# current_monitor_v1-2.net
KiCad netlist of a schematic drawn in EAGLE
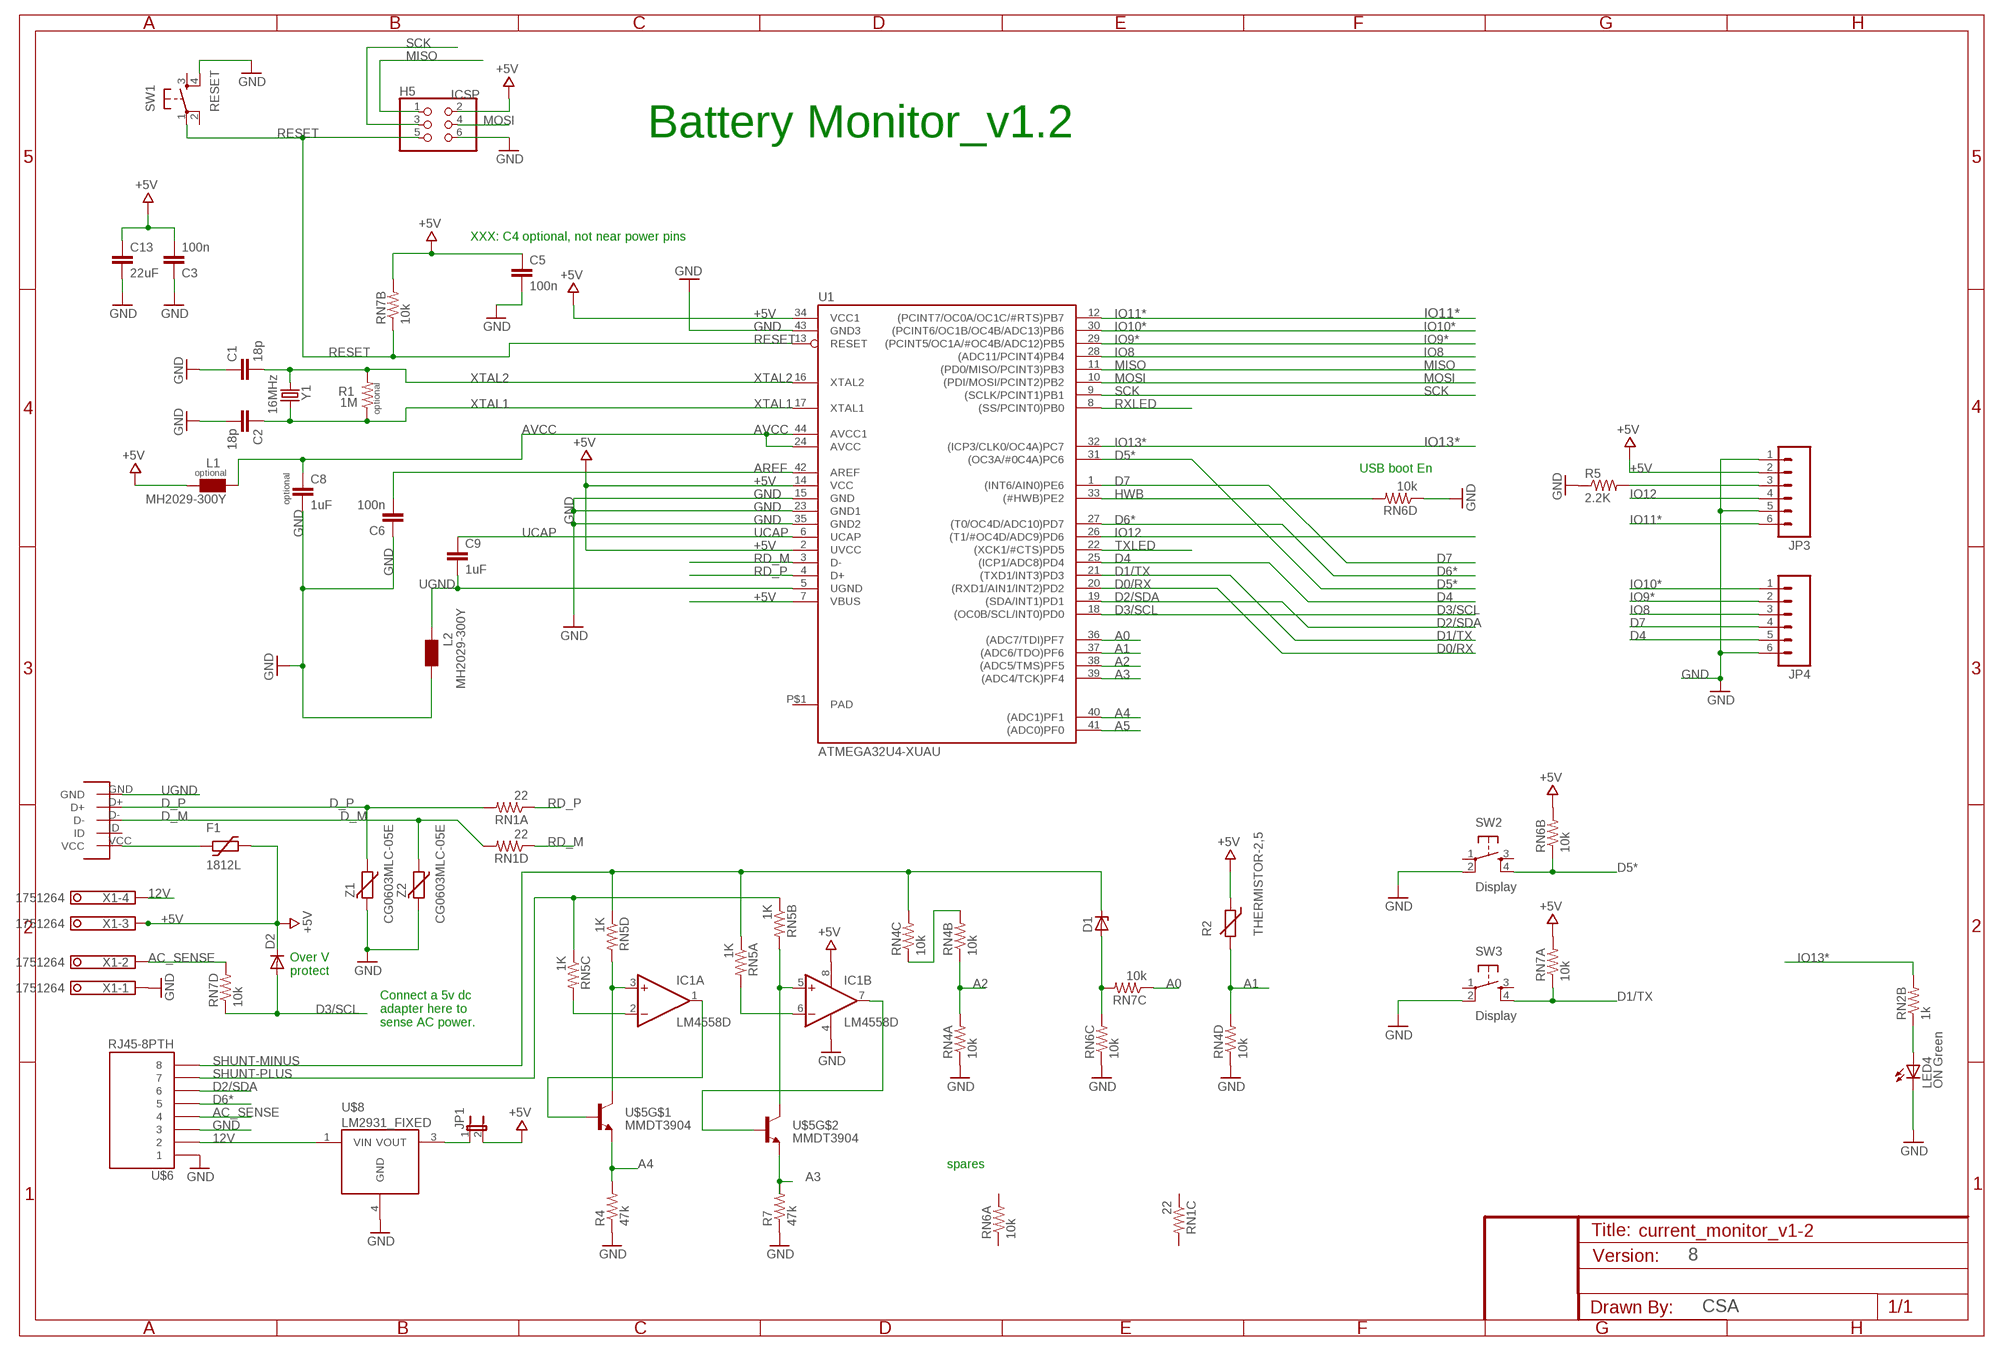
[diagram p0: schematic, sheet 1]

(export (version "E")
  (design (tool "Eeschema 10.0.6"))
  (components
    (comp (ref "C1")
      (value "18p")
      (footprint "eagle-import:0805")
      (libsource (lib "eagle-import") (part "CAP0805"))
    )
    (comp (ref "C2")
      (value "18p")
      (footprint "eagle-import:0805")
      (libsource (lib "eagle-import") (part "CAP0805"))
    )
    (comp (ref "C3")
      (value "100n")
      (footprint "eagle-import:0805")
      (libsource (lib "eagle-import") (part "CAP0805"))
    )
    (comp (ref "C5")
      (value "100n")
      (footprint "eagle-import:0805")
      (libsource (lib "eagle-import") (part "CAP0805"))
    )
    (comp (ref "C6")
      (value "100n")
      (footprint "eagle-import:0805")
      (libsource (lib "eagle-import") (part "CAP0805"))
    )
    (comp (ref "C8")
      (value "1uF")
      (footprint "eagle-import:0805")
      (libsource (lib "eagle-import") (part "CAP0805"))
    )
    (comp (ref "C9")
      (value "1uF")
      (footprint "eagle-import:0805")
      (libsource (lib "eagle-import") (part "CAP0805"))
    )
    (comp (ref "C13")
      (value "22uF")
      (footprint "eagle-import:1206")
      (libsource (lib "eagle-import") (part "CAP1206"))
    )
    (comp (ref "D1")
      (value "ZENER-DIODEZD-5")
      (footprint "eagle-import:ZDIO-5")
      (libsource (lib "eagle-import") (part "ZENER-DIODEZD-5"))
    )
    (comp (ref "D2")
      (value "DIODESMA")
      (footprint "eagle-import:SMA-DIODE")
      (libsource (lib "eagle-import") (part "DIODESMA"))
    )
    (comp (ref "F1")
      (value "1812L")
      (footprint "eagle-import:1812L")
      (libsource (lib "eagle-import") (part "1812L"))
    )
    (comp (ref "H5")
      (value "ICSP")
      (footprint "eagle-import:2X03")
      (libsource (lib "eagle-import") (part "PINHD-2X3"))
    )
    (comp (ref "IC1")
      (value "LM4558D")
      (footprint "eagle-import:SO08")
      (libsource (lib "eagle-import") (part "4558DLM"))
    )
    (comp (ref "JP1")
      (value "JUMPER-2-OLDPTH_LOCK")
      (footprint "eagle-import:1X02_LOCK")
      (libsource (lib "eagle-import") (part "JUMPER-2-OLDPTH_LOCK"))
    )
    (comp (ref "JP3")
      (value "M06FEMALE_LOCK")
      (footprint "eagle-import:1X06_FEMALE_LOCK.010")
      (libsource (lib "eagle-import") (part "M06FEMALE_LOCK"))
    )
    (comp (ref "JP4")
      (value "M06FEMALE_LOCK")
      (footprint "eagle-import:1X06_FEMALE_LOCK.010")
      (libsource (lib "eagle-import") (part "M06FEMALE_LOCK"))
    )
    (comp (ref "L1")
      (value "MH2029-300Y")
      (footprint "eagle-import:0805")
      (libsource (lib "eagle-import") (part "WE-CBF_0805"))
    )
    (comp (ref "L2")
      (value "MH2029-300Y")
      (footprint "eagle-import:0805")
      (libsource (lib "eagle-import") (part "WE-CBF_0805"))
    )
    (comp (ref "LED4")
      (value "ON Green")
      (footprint "eagle-import:LED0805")
      (libsource (lib "eagle-import") (part "LED0805"))
    )
    (comp (ref "R1")
      (value "1M")
      (footprint "eagle-import:0805")
      (libsource (lib "eagle-import") (part "RESISTOR0805-RES"))
    )
    (comp (ref "R2")
      (value "THERMISTOR-2,5")
      (footprint "eagle-import:RS-2,5")
      (libsource (lib "eagle-import") (part "THERMISTOR-2,5"))
    )
    (comp (ref "R4")
      (value "47k")
      (footprint "eagle-import:0805")
      (libsource (lib "eagle-import") (part "RESISTOR0805-RES"))
    )
    (comp (ref "R5")
      (value "2.2K")
      (footprint "eagle-import:0805")
      (libsource (lib "eagle-import") (part "RESISTOR0805-RES"))
    )
    (comp (ref "R7")
      (value "47k")
      (footprint "eagle-import:0805")
      (libsource (lib "eagle-import") (part "RESISTOR0805-RES"))
    )
    (comp (ref "RN1")
      (value "22")
      (footprint "eagle-import:CRA06S")
      (libsource (lib "eagle-import") (part "RESISTOR-ARRAYCRA06S"))
    )
    (comp (ref "RN2")
      (value "1k")
      (footprint "eagle-import:CRA06S")
      (libsource (lib "eagle-import") (part "RESISTOR-ARRAYCRA06S"))
    )
    (comp (ref "RN4")
      (value "10k")
      (footprint "eagle-import:CRA06S")
      (libsource (lib "eagle-import") (part "RESISTOR-ARRAYCRA06S"))
    )
    (comp (ref "RN5")
      (value "1K")
      (footprint "eagle-import:CRA06S")
      (libsource (lib "eagle-import") (part "RESISTOR-ARRAYCRA06S"))
    )
    (comp (ref "RN6")
      (value "10k")
      (footprint "eagle-import:CRA06S")
      (libsource (lib "eagle-import") (part "RESISTOR-ARRAYCRA06S"))
    )
    (comp (ref "RN7")
      (value "10k")
      (footprint "eagle-import:CRA06S")
      (libsource (lib "eagle-import") (part "RESISTOR-ARRAYCRA06S"))
    )
    (comp (ref "SW1")
      (value "RESET")
      (footprint "eagle-import:TACTILE-PTH")
      (libsource (lib "eagle-import") (part "TAC_SWITCHPTH"))
    )
    (comp (ref "SW2")
      (value "Display")
      (footprint "eagle-import:TACTILE-PTH")
      (libsource (lib "eagle-import") (part "TAC_SWITCHPTH"))
    )
    (comp (ref "SW3")
      (value "Display")
      (footprint "eagle-import:TACTILE-PTH")
      (libsource (lib "eagle-import") (part "TAC_SWITCHPTH"))
    )
    (comp (ref "U$5")
      (value "MMDT3904")
      (footprint "eagle-import:SOT363")
      (libsource (lib "eagle-import") (part "MMDT3904"))
    )
    (comp (ref "U$6")
      (value "RJ45-8PTH")
      (footprint "eagle-import:RJ45-8")
      (libsource (lib "eagle-import") (part "RJ45-8PTH"))
    )
    (comp (ref "U$8")
      (value "LM2931_FIXED")
      (footprint "eagle-import:DPAK")
      (libsource (lib "eagle-import") (part "LM2931_FIXED"))
    )
    (comp (ref "U$16")
      (value "USB-MICRO-B-DIGIKEY")
      (footprint "eagle-import:USB-MICRO-B-DIGIKEY")
      (libsource (lib "eagle-import") (part "USB-MICRO-B-DIGIKEY"))
    )
    (comp (ref "U1")
      (value "ATMEGA32U4-XUAU")
      (footprint "eagle-import:TQFP44-PAD")
      (libsource (lib "eagle-import") (part "ATMEGA32U4-XUAU"))
    )
    (comp (ref "X1")
      (value "1751264")
      (footprint "eagle-import:1751264")
      (libsource (lib "eagle-import") (part "1751264"))
    )
    (comp (ref "Y1")
      (value "16MHz")
      (footprint "eagle-import:HC49US")
      (libsource (lib "eagle-import") (part "CRYSTALHC49US"))
    )
    (comp (ref "Z1")
      (value "CG0603MLC-05E")
      (footprint "eagle-import:CT_CN0603")
      (libsource (lib "eagle-import") (part "VARISTORCN0603"))
    )
    (comp (ref "Z2")
      (value "CG0603MLC-05E")
      (footprint "eagle-import:CT_CN0603")
      (libsource (lib "eagle-import") (part "VARISTORCN0603"))
    )
  )
  (nets
    (net (code "1") (name "+5V") (class "Default")
      (node (ref "C13") (pin "1") (pinfunction "1_1") (pintype "passive"))
      (node (ref "C3") (pin "2") (pinfunction "2_2") (pintype "passive"))
      (node (ref "C5") (pin "1") (pinfunction "1_1") (pintype "passive"))
      (node (ref "D2") (pin "C") (pinfunction "C_C") (pintype "passive"))
      (node (ref "F1") (pin "P$2") (pinfunction "2_P$2") (pintype "passive"))
      (node (ref "H5") (pin "2") (pinfunction "2_2") (pintype "passive"))
      (node (ref "IC1") (pin "8") (pinfunction "V+_8") (pintype "power_in"))
      (node (ref "JP1") (pin "2") (pinfunction "2_2") (pintype "passive"))
      (node (ref "JP3") (pin "2") (pinfunction "2_2") (pintype "passive"))
      (node (ref "L1") (pin "1") (pinfunction "1_1") (pintype "passive"))
      (node (ref "R2") (pin "1") (pinfunction "1_1") (pintype "passive"))
      (node (ref "RN6") (pin "7") (pinfunction "2_7") (pintype "passive"))
      (node (ref "RN7") (pin "7") (pinfunction "2_7") (pintype "passive"))
      (node (ref "RN7") (pin "8") (pinfunction "2_8") (pintype "passive"))
      (node (ref "U1") (pin "14") (pinfunction "VCC_14") (pintype "power_in"))
      (node (ref "U1") (pin "2") (pinfunction "UVCC_2") (pintype "power_in"))
      (node (ref "U1") (pin "34") (pinfunction "VCC1_34") (pintype "power_in"))
      (node (ref "U1") (pin "7") (pinfunction "VBUS_7") (pintype "input"))
      (node (ref "X1") (pin "3") (pinfunction "K_3") (pintype "passive"))
    )
    (net (code "2") (name "/12V") (class "Default")
      (node (ref "U$6") (pin "2") (pinfunction "2_2") (pintype "bidirectional"))
      (node (ref "U$8") (pin "1") (pinfunction "VIN_1") (pintype "bidirectional"))
      (node (ref "X1") (pin "4") (pinfunction "K_4") (pintype "passive"))
    )
    (net (code "3") (name "/A0") (class "Default")
      (node (ref "D1") (pin "A") (pinfunction "A_A") (pintype "passive"))
      (node (ref "RN6") (pin "6") (pinfunction "2_6") (pintype "passive"))
      (node (ref "RN7") (pin "3") (pinfunction "1_3") (pintype "passive"))
      (node (ref "RN7") (pin "6") (pinfunction "2_6") (pintype "passive"))
      (node (ref "U1") (pin "36") (pinfunction "(ADC7/TDI)PF7_36") (pintype "bidirectional"))
    )
    (net (code "4") (name "/A1") (class "Default")
      (node (ref "R2") (pin "2") (pinfunction "2_2") (pintype "passive"))
      (node (ref "RN4") (pin "5") (pinfunction "2_5") (pintype "passive"))
      (node (ref "U1") (pin "37") (pinfunction "(ADC6/TDO)PF6_37") (pintype "bidirectional"))
    )
    (net (code "5") (name "/A2") (class "Default")
      (node (ref "RN4") (pin "2") (pinfunction "1_2") (pintype "passive"))
      (node (ref "RN4") (pin "8") (pinfunction "2_8") (pintype "passive"))
      (node (ref "U1") (pin "38") (pinfunction "(ADC5/TMS)PF5_38") (pintype "bidirectional"))
    )
    (net (code "6") (name "/A3") (class "Default")
      (node (ref "R7") (pin "2") (pinfunction "2_2") (pintype "passive"))
      (node (ref "U$5") (pin "1") (pinfunction "E_1") (pintype "passive"))
      (node (ref "U1") (pin "39") (pinfunction "(ADC4/TCK)PF4_39") (pintype "bidirectional"))
    )
    (net (code "7") (name "/A4") (class "Default")
      (node (ref "R4") (pin "2") (pinfunction "2_2") (pintype "passive"))
      (node (ref "U$5") (pin "4") (pinfunction "E_4") (pintype "passive"))
      (node (ref "U1") (pin "40") (pinfunction "(ADC1)PF1_40") (pintype "bidirectional"))
    )
    (net (code "8") (name "/A5") (class "Default")
      (node (ref "U1") (pin "41") (pinfunction "(ADC0)PF0_41") (pintype "bidirectional"))
    )
    (net (code "9") (name "/AC_SENSE") (class "Default")
      (node (ref "RN7") (pin "5") (pinfunction "2_5") (pintype "passive"))
      (node (ref "U$6") (pin "4") (pinfunction "4_4") (pintype "bidirectional"))
      (node (ref "X1") (pin "2") (pinfunction "K_2") (pintype "passive"))
    )
    (net (code "10") (name "/AREF") (class "Default")
      (node (ref "C6") (pin "2") (pinfunction "2_2") (pintype "passive"))
      (node (ref "U1") (pin "42") (pinfunction "AREF_42") (pintype "power_in"))
    )
    (net (code "11") (name "/AVCC") (class "Default")
      (node (ref "C8") (pin "1") (pinfunction "1_1") (pintype "passive"))
      (node (ref "L1") (pin "2") (pinfunction "2_2") (pintype "passive"))
      (node (ref "U1") (pin "24") (pinfunction "AVCC_24") (pintype "power_in"))
      (node (ref "U1") (pin "44") (pinfunction "AVCC1_44") (pintype "power_in"))
    )
    (net (code "12") (name "/D0{slash}RX") (class "Default")
      (node (ref "U1") (pin "20") (pinfunction "(RXD1/AIN1/INT2)PD2_20") (pintype "bidirectional"))
    )
    (net (code "13") (name "/D1{slash}TX") (class "Default")
      (node (ref "RN7") (pin "1") (pinfunction "1_1") (pintype "passive"))
      (node (ref "SW3") (pin "4") (pinfunction "4_4") (pintype "passive"))
      (node (ref "U1") (pin "21") (pinfunction "(TXD1/INT3)PD3_21") (pintype "bidirectional"))
    )
    (net (code "14") (name "/D2{slash}SDA") (class "Default")
      (node (ref "U$6") (pin "6") (pinfunction "6_6") (pintype "bidirectional"))
      (node (ref "U1") (pin "19") (pinfunction "(SDA/INT1)PD1_19") (pintype "bidirectional"))
    )
    (net (code "15") (name "/D3{slash}SCL") (class "Default")
      (node (ref "D2") (pin "A") (pinfunction "A_A") (pintype "passive"))
      (node (ref "RN7") (pin "4") (pinfunction "1_4") (pintype "passive"))
      (node (ref "U1") (pin "18") (pinfunction "(OC0B/SCL/INT0)PD0_18") (pintype "bidirectional"))
    )
    (net (code "16") (name "/D4") (class "Default")
      (node (ref "JP4") (pin "5") (pinfunction "5_5") (pintype "passive"))
      (node (ref "U1") (pin "25") (pinfunction "(ICP1/ADC8)PD4_25") (pintype "bidirectional"))
    )
    (net (code "17") (name "/D5*") (class "Default")
      (node (ref "RN6") (pin "2") (pinfunction "1_2") (pintype "passive"))
      (node (ref "SW2") (pin "4") (pinfunction "4_4") (pintype "passive"))
      (node (ref "U1") (pin "31") (pinfunction "(OC3A/#0C4A)PC6_31") (pintype "bidirectional"))
    )
    (net (code "18") (name "/D6*") (class "Default")
      (node (ref "U$6") (pin "5") (pinfunction "5_5") (pintype "bidirectional"))
      (node (ref "U1") (pin "27") (pinfunction "(T0/OC4D/ADC10)PD7_27") (pintype "bidirectional"))
    )
    (net (code "19") (name "/D7") (class "Default")
      (node (ref "JP4") (pin "4") (pinfunction "4_4") (pintype "passive"))
      (node (ref "U1") (pin "1") (pinfunction "(INT6/AIN0)PE6_1") (pintype "bidirectional"))
    )
    (net (code "20") (name "/D_M") (class "Default")
      (node (ref "RN1") (pin "5") (pinfunction "2_5") (pintype "passive"))
      (node (ref "U$16") (pin "D-") (pinfunction "D-_D-") (pintype "bidirectional"))
      (node (ref "Z2") (pin "1") (pinfunction "1_1") (pintype "passive"))
    )
    (net (code "21") (name "/D_P") (class "Default")
      (node (ref "RN1") (pin "8") (pinfunction "2_8") (pintype "passive"))
      (node (ref "U$16") (pin "D+") (pinfunction "D+_D+") (pintype "bidirectional"))
      (node (ref "Z1") (pin "1") (pinfunction "1_1") (pintype "passive"))
    )
    (net (code "22") (name "/HWB") (class "Default")
      (node (ref "RN6") (pin "5") (pinfunction "2_5") (pintype "passive"))
      (node (ref "U1") (pin "33") (pinfunction "(#HWB)PE2_33") (pintype "bidirectional"))
    )
    (net (code "23") (name "/IO8") (class "Default")
      (node (ref "JP4") (pin "3") (pinfunction "3_3") (pintype "passive"))
      (node (ref "U1") (pin "28") (pinfunction "(ADC11/PCINT4)PB4_28") (pintype "bidirectional"))
    )
    (net (code "24") (name "/IO9*") (class "Default")
      (node (ref "JP4") (pin "2") (pinfunction "2_2") (pintype "passive"))
      (node (ref "U1") (pin "29") (pinfunction "(PCINT5/OC1A/#OC4B/ADC12)PB5_29") (pintype "bidirectional"))
    )
    (net (code "25") (name "/IO10*") (class "Default")
      (node (ref "JP4") (pin "1") (pinfunction "1_1") (pintype "passive"))
      (node (ref "U1") (pin "30") (pinfunction "(PCINT6/OC1B/OC4B/ADC13)PB6_30") (pintype "bidirectional"))
    )
    (net (code "26") (name "/IO11*") (class "Default")
      (node (ref "JP3") (pin "6") (pinfunction "6_6") (pintype "passive"))
      (node (ref "U1") (pin "12") (pinfunction "(PCINT7/OC0A/OC1C/#RTS)PB7_12") (pintype "bidirectional"))
    )
    (net (code "27") (name "/IO12") (class "Default")
      (node (ref "JP3") (pin "4") (pinfunction "4_4") (pintype "passive"))
      (node (ref "U1") (pin "26") (pinfunction "(T1/#OC4D/ADC9)PD6_26") (pintype "bidirectional"))
    )
    (net (code "28") (name "/IO13*") (class "Default")
      (node (ref "RN2") (pin "7") (pinfunction "2_7") (pintype "passive"))
      (node (ref "U1") (pin "32") (pinfunction "(ICP3/CLK0/OC4A)PC7_32") (pintype "bidirectional"))
    )
    (net (code "29") (name "/MISO") (class "Default")
      (node (ref "H5") (pin "1") (pinfunction "1_1") (pintype "passive"))
      (node (ref "U1") (pin "11") (pinfunction "(PD0/MISO/PCINT3)PB3_11") (pintype "bidirectional"))
    )
    (net (code "30") (name "/MOSI") (class "Default")
      (node (ref "H5") (pin "4") (pinfunction "4_4") (pintype "passive"))
      (node (ref "U1") (pin "10") (pinfunction "(PDI/MOSI/PCINT2)PB2_10") (pintype "bidirectional"))
    )
    (net (code "31") (name "/PAD") (class "Default")
      (node (ref "U1") (pin "P$1") (pinfunction "PAD_P$1") (pintype "power_in"))
    )
    (net (code "32") (name "/RD_M") (class "Default")
      (node (ref "RN1") (pin "4") (pinfunction "1_4") (pintype "passive"))
      (node (ref "U1") (pin "3") (pinfunction "D-_3") (pintype "bidirectional"))
    )
    (net (code "33") (name "/RD_P") (class "Default")
      (node (ref "RN1") (pin "1") (pinfunction "1_1") (pintype "passive"))
      (node (ref "U1") (pin "4") (pinfunction "D+_4") (pintype "bidirectional"))
    )
    (net (code "34") (name "/RESET") (class "Default")
      (node (ref "H5") (pin "5") (pinfunction "5_5") (pintype "passive"))
      (node (ref "RN7") (pin "2") (pinfunction "1_2") (pintype "passive"))
      (node (ref "SW1") (pin "1") (pinfunction "1_1") (pintype "passive"))
      (node (ref "U1") (pin "13") (pinfunction "RESET_13") (pintype "input"))
    )
    (net (code "35") (name "/RXLED") (class "Default")
      (node (ref "U1") (pin "8") (pinfunction "(SS/PCINT0)PB0_8") (pintype "bidirectional"))
    )
    (net (code "36") (name "/SCK") (class "Default")
      (node (ref "H5") (pin "3") (pinfunction "3_3") (pintype "passive"))
      (node (ref "U1") (pin "9") (pinfunction "(SCLK/PCINT1)PB1_9") (pintype "bidirectional"))
    )
    (net (code "37") (name "/SHUNT-MINUS") (class "Default")
      (node (ref "D1") (pin "C") (pinfunction "C_C") (pintype "passive"))
      (node (ref "RN4") (pin "6") (pinfunction "2_6") (pintype "passive"))
      (node (ref "RN5") (pin "1") (pinfunction "1_1") (pintype "passive"))
      (node (ref "RN5") (pin "4") (pinfunction "1_4") (pintype "passive"))
      (node (ref "U$6") (pin "8") (pinfunction "8_8") (pintype "bidirectional"))
    )
    (net (code "38") (name "/SHUNT-PLUS") (class "Default")
      (node (ref "RN5") (pin "2") (pinfunction "1_2") (pintype "passive"))
      (node (ref "RN5") (pin "3") (pinfunction "1_3") (pintype "passive"))
      (node (ref "U$6") (pin "7") (pinfunction "7_7") (pintype "bidirectional"))
    )
    (net (code "39") (name "/TXLED") (class "Default")
      (node (ref "U1") (pin "22") (pinfunction "(XCK1/#CTS)PD5_22") (pintype "bidirectional"))
    )
    (net (code "40") (name "/UCAP") (class "Default")
      (node (ref "C9") (pin "1") (pinfunction "1_1") (pintype "passive"))
      (node (ref "U1") (pin "6") (pinfunction "UCAP_6") (pintype "passive"))
    )
    (net (code "41") (name "/UGND") (class "Default")
      (node (ref "C9") (pin "2") (pinfunction "2_2") (pintype "passive"))
      (node (ref "L2") (pin "1") (pinfunction "1_1") (pintype "passive"))
      (node (ref "U$16") (pin "GND") (pinfunction "GND_GND") (pintype "bidirectional"))
      (node (ref "U1") (pin "5") (pinfunction "UGND_5") (pintype "power_in"))
    )
    (net (code "42") (name "/XTAL1") (class "Default")
      (node (ref "C2") (pin "1") (pinfunction "1_1") (pintype "passive"))
      (node (ref "R1") (pin "1") (pinfunction "1_1") (pintype "passive"))
      (node (ref "U1") (pin "17") (pinfunction "XTAL1_17") (pintype "bidirectional"))
      (node (ref "Y1") (pin "2") (pinfunction "2_2") (pintype "passive"))
    )
    (net (code "43") (name "/XTAL2") (class "Default")
      (node (ref "C1") (pin "2") (pinfunction "2_2") (pintype "passive"))
      (node (ref "R1") (pin "2") (pinfunction "2_2") (pintype "passive"))
      (node (ref "U1") (pin "16") (pinfunction "XTAL2_16") (pintype "bidirectional"))
      (node (ref "Y1") (pin "1") (pinfunction "1_1") (pintype "passive"))
    )
    (net (code "44") (name "GND") (class "Default")
      (node (ref "C1") (pin "1") (pinfunction "1_1") (pintype "passive"))
      (node (ref "C13") (pin "2") (pinfunction "2_2") (pintype "passive"))
      (node (ref "C2") (pin "2") (pinfunction "2_2") (pintype "passive"))
      (node (ref "C3") (pin "1") (pinfunction "1_1") (pintype "passive"))
      (node (ref "C5") (pin "2") (pinfunction "2_2") (pintype "passive"))
      (node (ref "C6") (pin "1") (pinfunction "1_1") (pintype "passive"))
      (node (ref "C8") (pin "2") (pinfunction "2_2") (pintype "passive"))
      (node (ref "H5") (pin "6") (pinfunction "6_6") (pintype "passive"))
      (node (ref "IC1") (pin "4") (pinfunction "V-_4") (pintype "power_in"))
      (node (ref "JP3") (pin "1") (pinfunction "1_1") (pintype "passive"))
      (node (ref "JP3") (pin "5") (pinfunction "5_5") (pintype "passive"))
      (node (ref "JP4") (pin "6") (pinfunction "6_6") (pintype "passive"))
      (node (ref "L2") (pin "2") (pinfunction "2_2") (pintype "passive"))
      (node (ref "LED4") (pin "C") (pinfunction "C_C") (pintype "passive"))
      (node (ref "R4") (pin "1") (pinfunction "1_1") (pintype "passive"))
      (node (ref "R5") (pin "1") (pinfunction "1_1") (pintype "passive"))
      (node (ref "R7") (pin "1") (pinfunction "1_1") (pintype "passive"))
      (node (ref "RN4") (pin "1") (pinfunction "1_1") (pintype "passive"))
      (node (ref "RN4") (pin "4") (pinfunction "1_4") (pintype "passive"))
      (node (ref "RN6") (pin "3") (pinfunction "1_3") (pintype "passive"))
      (node (ref "RN6") (pin "4") (pinfunction "1_4") (pintype "passive"))
      (node (ref "SW1") (pin "4") (pinfunction "4_4") (pintype "passive"))
      (node (ref "SW2") (pin "2") (pinfunction "2_2") (pintype "passive"))
      (node (ref "SW3") (pin "2") (pinfunction "2_2") (pintype "passive"))
      (node (ref "U$6") (pin "1") (pinfunction "1_1") (pintype "bidirectional"))
      (node (ref "U$6") (pin "3") (pinfunction "3_3") (pintype "bidirectional"))
      (node (ref "U$8") (pin "4") (pinfunction "GND_4") (pintype "bidirectional"))
      (node (ref "U1") (pin "15") (pinfunction "GND_15") (pintype "power_in"))
      (node (ref "U1") (pin "23") (pinfunction "GND1_23") (pintype "power_in"))
      (node (ref "U1") (pin "35") (pinfunction "GND2_35") (pintype "power_in"))
      (node (ref "U1") (pin "43") (pinfunction "GND3_43") (pintype "power_in"))
      (node (ref "X1") (pin "1") (pinfunction "K_1") (pintype "passive"))
      (node (ref "Z1") (pin "2") (pinfunction "2_2") (pintype "passive"))
      (node (ref "Z2") (pin "2") (pinfunction "2_2") (pintype "passive"))
    )
    (net (code "45") (name "Net-(F1-1)") (class "Default")
      (node (ref "F1") (pin "P$1") (pinfunction "1_P$1") (pintype "passive"))
      (node (ref "U$16") (pin "VCC") (pinfunction "VCC_VCC") (pintype "bidirectional"))
    )
    (net (code "46") (name "Net-(IC1A-+IN)") (class "Default")
      (node (ref "IC1") (pin "3") (pinfunction "+IN_3") (pintype "input"))
      (node (ref "RN5") (pin "5") (pinfunction "2_5") (pintype "passive"))
      (node (ref "U$5") (pin "3") (pinfunction "C_3") (pintype "passive"))
    )
    (net (code "47") (name "Net-(IC1A--IN)") (class "Default")
      (node (ref "IC1") (pin "2") (pinfunction "-IN_2") (pintype "input"))
      (node (ref "RN5") (pin "6") (pinfunction "2_6") (pintype "passive"))
    )
    (net (code "48") (name "Net-(IC1A-OUT)") (class "Default")
      (node (ref "IC1") (pin "1") (pinfunction "OUT_1") (pintype "output"))
      (node (ref "U$5") (pin "5") (pinfunction "B_5") (pintype "passive"))
    )
    (net (code "49") (name "Net-(IC1B-+IN)") (class "Default")
      (node (ref "IC1") (pin "5") (pinfunction "+IN_5") (pintype "input"))
      (node (ref "RN5") (pin "7") (pinfunction "2_7") (pintype "passive"))
      (node (ref "U$5") (pin "6") (pinfunction "C_6") (pintype "passive"))
    )
    (net (code "50") (name "Net-(IC1B--IN)") (class "Default")
      (node (ref "IC1") (pin "6") (pinfunction "-IN_6") (pintype "input"))
      (node (ref "RN5") (pin "8") (pinfunction "2_8") (pintype "passive"))
    )
    (net (code "51") (name "Net-(IC1B-OUT)") (class "Default")
      (node (ref "IC1") (pin "7") (pinfunction "OUT_7") (pintype "output"))
      (node (ref "U$5") (pin "2") (pinfunction "B_2") (pintype "passive"))
    )
    (net (code "52") (name "Net-(JP3-Pad3)") (class "Default")
      (node (ref "JP3") (pin "3") (pinfunction "3_3") (pintype "passive"))
      (node (ref "R5") (pin "2") (pinfunction "2_2") (pintype "passive"))
    )
    (net (code "53") (name "Net-(RN2B-1)") (class "Default")
      (node (ref "LED4") (pin "A") (pinfunction "A_A") (pintype "passive"))
      (node (ref "RN2") (pin "2") (pinfunction "1_2") (pintype "passive"))
    )
    (net (code "54") (name "Net-(RN4B-2)") (class "Default")
      (node (ref "RN4") (pin "3") (pinfunction "1_3") (pintype "passive"))
      (node (ref "RN4") (pin "7") (pinfunction "2_7") (pintype "passive"))
    )
    (net (code "55") (name "Net-(U$8-VOUT)") (class "Default")
      (node (ref "JP1") (pin "1") (pinfunction "1_1") (pintype "passive"))
      (node (ref "U$8") (pin "3") (pinfunction "VOUT_3") (pintype "bidirectional"))
    )
    (net (code "56") (name "unconnected-(RN1C-1-Pad3)") (class "Default")
      (node (ref "RN1") (pin "3") (pinfunction "1_3") (pintype "passive"))
    )
    (net (code "57") (name "unconnected-(RN1C-2-Pad6)") (class "Default")
      (node (ref "RN1") (pin "6") (pinfunction "2_6") (pintype "passive"))
    )
    (net (code "58") (name "unconnected-(RN6-Pad1)") (class "Default")
      (node (ref "RN6") (pin "1") (pinfunction "1_1") (pintype "passive"))
    )
    (net (code "59") (name "unconnected-(RN6A-2-Pad8)") (class "Default")
      (node (ref "RN6") (pin "8") (pinfunction "2_8") (pintype "passive"))
    )
    (net (code "60") (name "unconnected-(SW1-Pad2)") (class "Default")
      (node (ref "SW1") (pin "2") (pinfunction "2_2") (pintype "passive"))
    )
    (net (code "61") (name "unconnected-(SW1-Pad3)") (class "Default")
      (node (ref "SW1") (pin "3") (pinfunction "3_3") (pintype "passive"))
    )
    (net (code "62") (name "unconnected-(SW2-Pad1)") (class "Default")
      (node (ref "SW2") (pin "1") (pinfunction "1_1") (pintype "passive"))
    )
    (net (code "63") (name "unconnected-(SW2-Pad3)") (class "Default")
      (node (ref "SW2") (pin "3") (pinfunction "3_3") (pintype "passive"))
    )
    (net (code "64") (name "unconnected-(SW3-Pad1)") (class "Default")
      (node (ref "SW3") (pin "1") (pinfunction "1_1") (pintype "passive"))
    )
    (net (code "65") (name "unconnected-(SW3-Pad3)") (class "Default")
      (node (ref "SW3") (pin "3") (pinfunction "3_3") (pintype "passive"))
    )
    (net (code "66") (name "unconnected-(U$16-PadID)") (class "Default")
      (node (ref "U$16") (pin "ID") (pinfunction "ID_ID") (pintype "bidirectional"))
    )
  )
)
